# circuit_etudiant_2025.net
KiCad netlist of a schematic drawn in Altium Designer
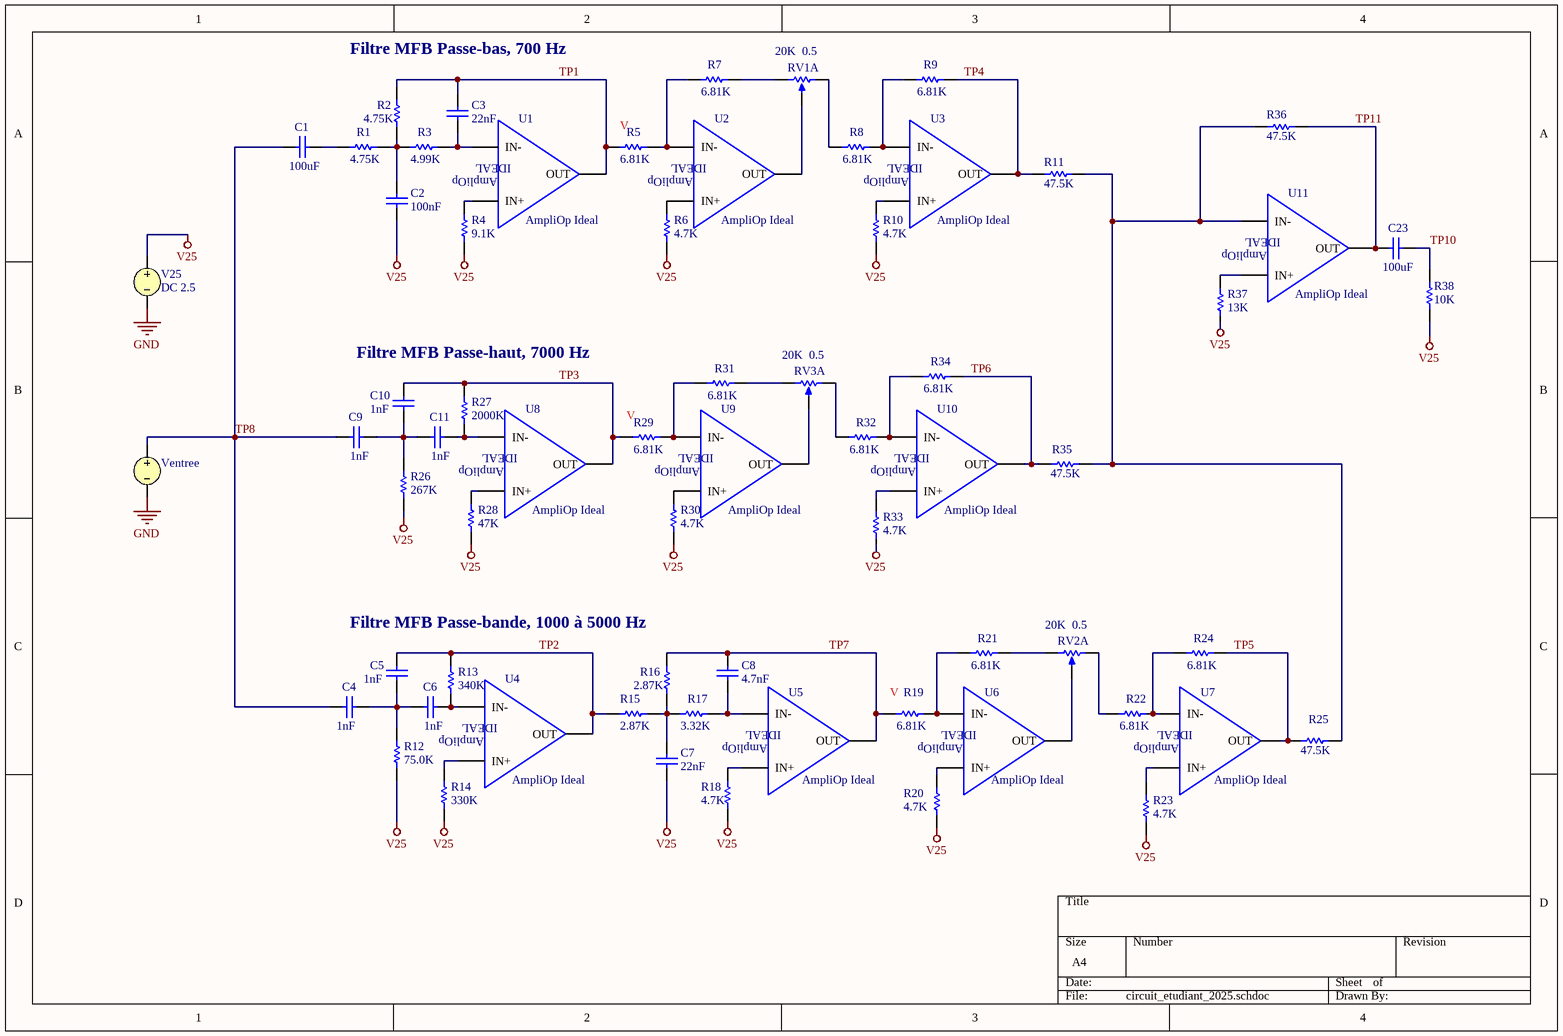
[diagram p0: circuit_etudiant_2025.schdoc]

(export (version "E")
  (design (tool "Eeschema 10.0.6"))
  (components
    (comp (ref "C1")
      (value "100uF")
      (footprint "RAD-0.3")
      (description "Capacitor")
      (fields (field (name "Comment") "Cap") (field (name "PUBLISHER") "Altium Limited"))
      (libsource (lib "Miscellaneous Devices") (part "Cap"))
    )
    (comp (ref "C2")
      (value "100nF")
      (footprint "RAD-0.3")
      (description "Capacitor")
      (fields (field (name "Comment") "Cap") (field (name "PUBLISHER") "Altium Limited"))
      (libsource (lib "Miscellaneous Devices") (part "Cap"))
    )
    (comp (ref "C3")
      (value "22nF")
      (footprint "RAD-0.3")
      (description "Capacitor")
      (fields (field (name "Comment") "Cap") (field (name "PUBLISHER") "Altium Limited"))
      (libsource (lib "Miscellaneous Devices") (part "Cap"))
    )
    (comp (ref "C4")
      (value "1nF")
      (footprint "RAD-0.3")
      (description "Capacitor")
      (fields (field (name "Comment") "Cap") (field (name "PUBLISHER") "Altium Limited"))
      (libsource (lib "Miscellaneous Devices") (part "Cap"))
    )
    (comp (ref "C5")
      (value "1nF")
      (footprint "RAD-0.3")
      (description "Capacitor")
      (fields (field (name "Comment") "Cap") (field (name "PUBLISHER") "Altium Limited"))
      (libsource (lib "Miscellaneous Devices") (part "Cap"))
    )
    (comp (ref "C6")
      (value "1nF")
      (footprint "RAD-0.3")
      (description "Capacitor")
      (fields (field (name "Comment") "Cap") (field (name "PUBLISHER") "Altium Limited"))
      (libsource (lib "Miscellaneous Devices") (part "Cap"))
    )
    (comp (ref "C7")
      (value "22nF")
      (footprint "RAD-0.3")
      (description "Capacitor")
      (fields (field (name "Comment") "Cap") (field (name "PUBLISHER") "Altium Limited"))
      (libsource (lib "Miscellaneous Devices") (part "Cap"))
    )
    (comp (ref "C8")
      (value "4.7nF")
      (footprint "RAD-0.3")
      (description "Capacitor")
      (fields (field (name "Comment") "Cap") (field (name "PUBLISHER") "Altium Limited"))
      (libsource (lib "Miscellaneous Devices") (part "Cap"))
    )
    (comp (ref "C9")
      (value "1nF")
      (footprint "RAD-0.3")
      (description "Capacitor")
      (fields (field (name "Comment") "Cap") (field (name "PUBLISHER") "Altium Limited"))
      (libsource (lib "Miscellaneous Devices") (part "Cap"))
    )
    (comp (ref "C10")
      (value "1nF")
      (footprint "RAD-0.3")
      (description "Capacitor")
      (fields (field (name "Comment") "Cap") (field (name "PUBLISHER") "Altium Limited"))
      (libsource (lib "Miscellaneous Devices") (part "Cap"))
    )
    (comp (ref "C11")
      (value "1nF")
      (footprint "RAD-0.3")
      (description "Capacitor")
      (fields (field (name "Comment") "Cap") (field (name "PUBLISHER") "Altium Limited"))
      (libsource (lib "Miscellaneous Devices") (part "Cap"))
    )
    (comp (ref "C23")
      (value "100uF")
      (footprint "RAD-0.3")
      (description "Capacitor")
      (fields (field (name "Comment") "Cap") (field (name "PUBLISHER") "Altium Limited"))
      (libsource (lib "Miscellaneous Devices") (part "Cap"))
    )
    (comp (ref "R1")
      (value "4.75K")
      (footprint "AXIAL-0.3")
      (description "Resistor")
      (fields (field (name "Comment") "Res1") (field (name "PUBLISHER") "Altium Limited"))
      (libsource (lib "Miscellaneous Devices") (part "Res1"))
    )
    (comp (ref "R2")
      (value "4.75K")
      (footprint "AXIAL-0.3")
      (description "Resistor")
      (fields (field (name "Comment") "Res1") (field (name "PUBLISHER") "Altium Limited"))
      (libsource (lib "Miscellaneous Devices") (part "Res1"))
    )
    (comp (ref "R3")
      (value "4.99K")
      (footprint "AXIAL-0.3")
      (description "Resistor")
      (fields (field (name "Comment") "Res1") (field (name "PUBLISHER") "Altium Limited"))
      (libsource (lib "Miscellaneous Devices") (part "Res1"))
    )
    (comp (ref "R4")
      (value "9.1K")
      (footprint "AXIAL-0.3")
      (description "Resistor")
      (fields (field (name "Comment") "Res1") (field (name "PUBLISHER") "Altium Limited"))
      (libsource (lib "Miscellaneous Devices") (part "Res1"))
    )
    (comp (ref "R5")
      (value "6.81K")
      (footprint "AXIAL-0.3")
      (description "Resistor")
      (fields (field (name "Comment") "Res1") (field (name "PUBLISHER") "Altium Limited"))
      (libsource (lib "Miscellaneous Devices") (part "Res1"))
    )
    (comp (ref "R6")
      (value "4.7K")
      (footprint "AXIAL-0.3")
      (description "Resistor")
      (fields (field (name "Comment") "Res1") (field (name "PUBLISHER") "Altium Limited"))
      (libsource (lib "Miscellaneous Devices") (part "Res1"))
    )
    (comp (ref "R7")
      (value "6.81K")
      (footprint "AXIAL-0.3")
      (description "Resistor")
      (fields (field (name "Comment") "Res1") (field (name "PUBLISHER") "Altium Limited"))
      (libsource (lib "Miscellaneous Devices") (part "Res1"))
    )
    (comp (ref "R8")
      (value "6.81K")
      (footprint "AXIAL-0.3")
      (description "Resistor")
      (fields (field (name "Comment") "Res1") (field (name "PUBLISHER") "Altium Limited"))
      (libsource (lib "Miscellaneous Devices") (part "Res1"))
    )
    (comp (ref "R9")
      (value "6.81K")
      (footprint "AXIAL-0.3")
      (description "Resistor")
      (fields (field (name "Comment") "Res1") (field (name "PUBLISHER") "Altium Limited"))
      (libsource (lib "Miscellaneous Devices") (part "Res1"))
    )
    (comp (ref "R10")
      (value "4.7K")
      (footprint "AXIAL-0.3")
      (description "Resistor")
      (fields (field (name "Comment") "Res1") (field (name "PUBLISHER") "Altium Limited"))
      (libsource (lib "Miscellaneous Devices") (part "Res1"))
    )
    (comp (ref "R11")
      (value "47.5K")
      (footprint "AXIAL-0.3")
      (description "Resistor")
      (fields (field (name "Comment") "Res1") (field (name "PUBLISHER") "Altium Limited"))
      (libsource (lib "Miscellaneous Devices") (part "Res1"))
    )
    (comp (ref "R12")
      (value "75.0K")
      (footprint "AXIAL-0.3")
      (description "Resistor")
      (fields (field (name "Comment") "Res1") (field (name "PUBLISHER") "Altium Limited"))
      (libsource (lib "Miscellaneous Devices") (part "Res1"))
    )
    (comp (ref "R13")
      (value "340K")
      (footprint "AXIAL-0.3")
      (description "Resistor")
      (fields (field (name "Comment") "Res1") (field (name "PUBLISHER") "Altium Limited"))
      (libsource (lib "Miscellaneous Devices") (part "Res1"))
    )
    (comp (ref "R14")
      (value "330K")
      (footprint "AXIAL-0.3")
      (description "Resistor")
      (fields (field (name "Comment") "Res1") (field (name "PUBLISHER") "Altium Limited"))
      (libsource (lib "Miscellaneous Devices") (part "Res1"))
    )
    (comp (ref "R15")
      (value "2.87K")
      (footprint "AXIAL-0.3")
      (description "Resistor")
      (fields (field (name "Comment") "Res1") (field (name "PUBLISHER") "Altium Limited"))
      (libsource (lib "Miscellaneous Devices") (part "Res1"))
    )
    (comp (ref "R16")
      (value "2.87K")
      (footprint "AXIAL-0.3")
      (description "Resistor")
      (fields (field (name "Comment") "Res1") (field (name "PUBLISHER") "Altium Limited"))
      (libsource (lib "Miscellaneous Devices") (part "Res1"))
    )
    (comp (ref "R17")
      (value "3.32K")
      (footprint "AXIAL-0.3")
      (description "Resistor")
      (fields (field (name "Comment") "Res1") (field (name "PUBLISHER") "Altium Limited"))
      (libsource (lib "Miscellaneous Devices") (part "Res1"))
    )
    (comp (ref "R18")
      (value "4.7K")
      (footprint "AXIAL-0.3")
      (description "Resistor")
      (fields (field (name "Comment") "Res1") (field (name "PUBLISHER") "Altium Limited"))
      (libsource (lib "Miscellaneous Devices") (part "Res1"))
    )
    (comp (ref "R19")
      (value "6.81K")
      (footprint "AXIAL-0.3")
      (description "Resistor")
      (fields (field (name "Comment") "Res1") (field (name "PUBLISHER") "Altium Limited"))
      (libsource (lib "Miscellaneous Devices") (part "Res1"))
    )
    (comp (ref "R20")
      (value "4.7K")
      (footprint "AXIAL-0.3")
      (description "Resistor")
      (fields (field (name "Comment") "Res1") (field (name "PUBLISHER") "Altium Limited"))
      (libsource (lib "Miscellaneous Devices") (part "Res1"))
    )
    (comp (ref "R21")
      (value "6.81K")
      (footprint "AXIAL-0.3")
      (description "Resistor")
      (fields (field (name "Comment") "Res1") (field (name "PUBLISHER") "Altium Limited"))
      (libsource (lib "Miscellaneous Devices") (part "Res1"))
    )
    (comp (ref "R22")
      (value "6.81K")
      (footprint "AXIAL-0.3")
      (description "Resistor")
      (fields (field (name "Comment") "Res1") (field (name "PUBLISHER") "Altium Limited"))
      (libsource (lib "Miscellaneous Devices") (part "Res1"))
    )
    (comp (ref "R23")
      (value "4.7K")
      (footprint "AXIAL-0.3")
      (description "Resistor")
      (fields (field (name "Comment") "Res1") (field (name "PUBLISHER") "Altium Limited"))
      (libsource (lib "Miscellaneous Devices") (part "Res1"))
    )
    (comp (ref "R24")
      (value "6.81K")
      (footprint "AXIAL-0.3")
      (description "Resistor")
      (fields (field (name "Comment") "Res1") (field (name "PUBLISHER") "Altium Limited"))
      (libsource (lib "Miscellaneous Devices") (part "Res1"))
    )
    (comp (ref "R25")
      (value "47.5K")
      (footprint "AXIAL-0.3")
      (description "Resistor")
      (fields (field (name "Comment") "Res1") (field (name "PUBLISHER") "Altium Limited"))
      (libsource (lib "Miscellaneous Devices") (part "Res1"))
    )
    (comp (ref "R26")
      (value "267K")
      (footprint "AXIAL-0.3")
      (description "Resistor")
      (fields (field (name "Comment") "Res1") (field (name "PUBLISHER") "Altium Limited"))
      (libsource (lib "Miscellaneous Devices") (part "Res1"))
    )
    (comp (ref "R27")
      (value "2000K")
      (footprint "AXIAL-0.3")
      (description "Resistor")
      (fields (field (name "Comment") "Res1") (field (name "PUBLISHER") "Altium Limited"))
      (libsource (lib "Miscellaneous Devices") (part "Res1"))
    )
    (comp (ref "R28")
      (value "47K")
      (footprint "AXIAL-0.3")
      (description "Resistor")
      (fields (field (name "Comment") "Res1") (field (name "PUBLISHER") "Altium Limited"))
      (libsource (lib "Miscellaneous Devices") (part "Res1"))
    )
    (comp (ref "R29")
      (value "6.81K")
      (footprint "AXIAL-0.3")
      (description "Resistor")
      (fields (field (name "Comment") "Res1") (field (name "PUBLISHER") "Altium Limited"))
      (libsource (lib "Miscellaneous Devices") (part "Res1"))
    )
    (comp (ref "R30")
      (value "4.7K")
      (footprint "AXIAL-0.3")
      (description "Resistor")
      (fields (field (name "Comment") "Res1") (field (name "PUBLISHER") "Altium Limited"))
      (libsource (lib "Miscellaneous Devices") (part "Res1"))
    )
    (comp (ref "R31")
      (value "6.81K")
      (footprint "AXIAL-0.3")
      (description "Resistor")
      (fields (field (name "Comment") "Res1") (field (name "PUBLISHER") "Altium Limited"))
      (libsource (lib "Miscellaneous Devices") (part "Res1"))
    )
    (comp (ref "R32")
      (value "6.81K")
      (footprint "AXIAL-0.3")
      (description "Resistor")
      (fields (field (name "Comment") "Res1") (field (name "PUBLISHER") "Altium Limited"))
      (libsource (lib "Miscellaneous Devices") (part "Res1"))
    )
    (comp (ref "R33")
      (value "4.7K")
      (footprint "AXIAL-0.3")
      (description "Resistor")
      (fields (field (name "Comment") "Res1") (field (name "PUBLISHER") "Altium Limited"))
      (libsource (lib "Miscellaneous Devices") (part "Res1"))
    )
    (comp (ref "R34")
      (value "6.81K")
      (footprint "AXIAL-0.3")
      (description "Resistor")
      (fields (field (name "Comment") "Res1") (field (name "PUBLISHER") "Altium Limited"))
      (libsource (lib "Miscellaneous Devices") (part "Res1"))
    )
    (comp (ref "R35")
      (value "47.5K")
      (footprint "AXIAL-0.3")
      (description "Resistor")
      (fields (field (name "Comment") "Res1") (field (name "PUBLISHER") "Altium Limited"))
      (libsource (lib "Miscellaneous Devices") (part "Res1"))
    )
    (comp (ref "R36")
      (value "47.5K")
      (footprint "AXIAL-0.3")
      (description "Resistor")
      (fields (field (name "Comment") "Res1") (field (name "PUBLISHER") "Altium Limited"))
      (libsource (lib "Miscellaneous Devices") (part "Res1"))
    )
    (comp (ref "R37")
      (value "13K")
      (footprint "AXIAL-0.3")
      (description "Resistor")
      (fields (field (name "Comment") "Res1") (field (name "PUBLISHER") "Altium Limited"))
      (libsource (lib "Miscellaneous Devices") (part "Res1"))
    )
    (comp (ref "R38")
      (value "10K")
      (footprint "AXIAL-0.3")
      (description "Resistor")
      (fields (field (name "Comment") "Res1") (field (name "PUBLISHER") "Altium Limited"))
      (libsource (lib "Miscellaneous Devices") (part "Res1"))
    )
    (comp (ref "RV1A")
      (value "20K")
      (footprint "VR5")
      (description "Potentiometer")
      (fields
        (field (name "SET POSITION") "0.5")
        (field (name "Comment") "RPot")
        (field (name "PUBLISHER") "Altium Limited")
      )
      (libsource (lib "Miscellaneous Devices") (part "RPot"))
    )
    (comp (ref "RV2A")
      (value "20K")
      (footprint "VR5")
      (description "Potentiometer")
      (fields
        (field (name "SET POSITION") "0.5")
        (field (name "Comment") "RPot")
        (field (name "PUBLISHER") "Altium Limited")
      )
      (libsource (lib "Miscellaneous Devices") (part "RPot"))
    )
    (comp (ref "RV3A")
      (value "20K")
      (footprint "VR5")
      (description "Potentiometer")
      (fields
        (field (name "SET POSITION") "0.5")
        (field (name "Comment") "RPot")
        (field (name "PUBLISHER") "Altium Limited")
      )
      (libsource (lib "Miscellaneous Devices") (part "RPot"))
    )
    (comp (ref "U1") (value "AmpliOp Ideal") (libsource (lib "Librarie_S2") (part "AmpliOp_ideal")))
    (comp (ref "U2") (value "AmpliOp Ideal") (libsource (lib "Librarie_S2") (part "AmpliOp_ideal")))
    (comp (ref "U3") (value "AmpliOp Ideal") (libsource (lib "Librarie_S2") (part "AmpliOp_ideal")))
    (comp (ref "U4") (value "AmpliOp Ideal") (libsource (lib "Librarie_S2") (part "AmpliOp_ideal")))
    (comp (ref "U5") (value "AmpliOp Ideal") (libsource (lib "Librarie_S2") (part "AmpliOp_ideal")))
    (comp (ref "U6") (value "AmpliOp Ideal") (libsource (lib "Librarie_S2") (part "AmpliOp_ideal")))
    (comp (ref "U7") (value "AmpliOp Ideal") (libsource (lib "Librarie_S2") (part "AmpliOp_ideal")))
    (comp (ref "U8") (value "AmpliOp Ideal") (libsource (lib "Librarie_S2") (part "AmpliOp_ideal")))
    (comp (ref "U9") (value "AmpliOp Ideal") (libsource (lib "Librarie_S2") (part "AmpliOp_ideal")))
    (comp (ref "U10") (value "AmpliOp Ideal") (libsource (lib "Librarie_S2") (part "AmpliOp_ideal")))
    (comp (ref "U11") (value "AmpliOp Ideal") (libsource (lib "Librarie_S2") (part "AmpliOp_ideal")))
    (comp (ref "V25")
      (value "DC 2.5")
      (description "Voltage Source")
      (fields (field (name "PUBLISHER") "Altium Limited"))
      (libsource (lib "Simulation Generic Components") (part "VSRC"))
    )
    (comp (ref "Ventree")
      (value "SIN(0 1 1Meg 0 0 0)")
      (description "Voltage Source")
      (fields (field (name "PUBLISHER") "Altium Limited"))
      (libsource (lib "Simulation Generic Components") (part "VSRC"))
    )
  )
  (nets
    (net (code "1") (name "/TP1") (class "Default")
      (node (ref "C3") (pin "1") (pinfunction "1_1") (pintype "passive"))
      (node (ref "R2") (pin "1") (pinfunction "1_1") (pintype "passive"))
      (node (ref "R5") (pin "1") (pinfunction "1_1") (pintype "passive"))
      (node (ref "U1") (pin "3") (pinfunction "OUT_3") (pintype "passive"))
    )
    (net (code "2") (name "/TP2") (class "Default")
      (node (ref "C5") (pin "1") (pinfunction "1_1") (pintype "passive"))
      (node (ref "R13") (pin "1") (pinfunction "1_1") (pintype "passive"))
      (node (ref "R15") (pin "1") (pinfunction "1_1") (pintype "passive"))
      (node (ref "U4") (pin "3") (pinfunction "OUT_3") (pintype "passive"))
    )
    (net (code "3") (name "/TP3") (class "Default")
      (node (ref "C10") (pin "1") (pinfunction "1_1") (pintype "passive"))
      (node (ref "R27") (pin "1") (pinfunction "1_1") (pintype "passive"))
      (node (ref "R29") (pin "1") (pinfunction "1_1") (pintype "passive"))
      (node (ref "U8") (pin "3") (pinfunction "OUT_3") (pintype "passive"))
    )
    (net (code "4") (name "/TP4") (class "Default")
      (node (ref "R11") (pin "1") (pinfunction "1_1") (pintype "passive"))
      (node (ref "R9") (pin "2") (pinfunction "2_2") (pintype "passive"))
      (node (ref "U3") (pin "3") (pinfunction "OUT_3") (pintype "passive"))
    )
    (net (code "5") (name "/TP5") (class "Default")
      (node (ref "R24") (pin "2") (pinfunction "2_2") (pintype "passive"))
      (node (ref "R25") (pin "1") (pinfunction "1_1") (pintype "passive"))
      (node (ref "U7") (pin "3") (pinfunction "OUT_3") (pintype "passive"))
    )
    (net (code "6") (name "/TP6") (class "Default")
      (node (ref "R34") (pin "2") (pinfunction "2_2") (pintype "passive"))
      (node (ref "R35") (pin "1") (pinfunction "1_1") (pintype "passive"))
      (node (ref "U10") (pin "3") (pinfunction "OUT_3") (pintype "passive"))
    )
    (net (code "7") (name "/TP7") (class "Default")
      (node (ref "C8") (pin "1") (pinfunction "1_1") (pintype "passive"))
      (node (ref "R16") (pin "1") (pinfunction "1_1") (pintype "passive"))
      (node (ref "R19") (pin "1") (pinfunction "1_1") (pintype "passive"))
      (node (ref "U5") (pin "3") (pinfunction "OUT_3") (pintype "passive"))
    )
    (net (code "8") (name "/TP8") (class "Default")
      (node (ref "C1") (pin "1") (pinfunction "1_1") (pintype "passive"))
      (node (ref "C4") (pin "1") (pinfunction "1_1") (pintype "passive"))
      (node (ref "C9") (pin "1") (pinfunction "1_1") (pintype "passive"))
      (node (ref "Ventree") (pin "1") (pinfunction "1_1") (pintype "passive"))
    )
    (net (code "9") (name "/TP10") (class "Default")
      (node (ref "C23") (pin "2") (pinfunction "2_2") (pintype "passive"))
      (node (ref "R38") (pin "2") (pinfunction "2_2") (pintype "passive"))
    )
    (net (code "10") (name "/TP11") (class "Default")
      (node (ref "C23") (pin "1") (pinfunction "1_1") (pintype "passive"))
      (node (ref "R36") (pin "2") (pinfunction "2_2") (pintype "passive"))
      (node (ref "U11") (pin "3") (pinfunction "OUT_3") (pintype "passive"))
    )
    (net (code "11") (name "GND") (class "Default")
      (node (ref "V25") (pin "2") (pinfunction "2_2") (pintype "passive"))
      (node (ref "Ventree") (pin "2") (pinfunction "2_2") (pintype "passive"))
    )
    (net (code "12") (name "Net-(C1-Pad2)") (class "Default")
      (node (ref "C1") (pin "2") (pinfunction "2_2") (pintype "passive"))
      (node (ref "R1") (pin "1") (pinfunction "1_1") (pintype "passive"))
    )
    (net (code "13") (name "Net-(C2-Pad1)") (class "Default")
      (node (ref "C2") (pin "1") (pinfunction "1_1") (pintype "passive"))
      (node (ref "R1") (pin "2") (pinfunction "2_2") (pintype "passive"))
      (node (ref "R2") (pin "2") (pinfunction "2_2") (pintype "passive"))
      (node (ref "R3") (pin "1") (pinfunction "1_1") (pintype "passive"))
    )
    (net (code "14") (name "Net-(C4-Pad2)") (class "Default")
      (node (ref "C4") (pin "2") (pinfunction "2_2") (pintype "passive"))
      (node (ref "C5") (pin "2") (pinfunction "2_2") (pintype "passive"))
      (node (ref "C6") (pin "1") (pinfunction "1_1") (pintype "passive"))
      (node (ref "R12") (pin "1") (pinfunction "1_1") (pintype "passive"))
    )
    (net (code "15") (name "Net-(C7-Pad1)") (class "Default")
      (node (ref "C7") (pin "1") (pinfunction "1_1") (pintype "passive"))
      (node (ref "R15") (pin "2") (pinfunction "2_2") (pintype "passive"))
      (node (ref "R16") (pin "2") (pinfunction "2_2") (pintype "passive"))
      (node (ref "R17") (pin "1") (pinfunction "1_1") (pintype "passive"))
    )
    (net (code "16") (name "Net-(C10-Pad2)") (class "Default")
      (node (ref "C10") (pin "2") (pinfunction "2_2") (pintype "passive"))
      (node (ref "C11") (pin "1") (pinfunction "1_1") (pintype "passive"))
      (node (ref "C9") (pin "2") (pinfunction "2_2") (pintype "passive"))
      (node (ref "R26") (pin "1") (pinfunction "1_1") (pintype "passive"))
    )
    (net (code "17") (name "Net-(RV1A-BOT)") (class "Default")
      (node (ref "R8") (pin "1") (pinfunction "1_1") (pintype "passive"))
      (node (ref "RV1A") (pin "2") (pinfunction "BOT_2") (pintype "passive"))
    )
    (net (code "18") (name "Net-(RV1A-TAP)") (class "Default")
      (node (ref "RV1A") (pin "3") (pinfunction "TAP_3") (pintype "passive"))
      (node (ref "U2") (pin "3") (pinfunction "OUT_3") (pintype "passive"))
    )
    (net (code "19") (name "Net-(RV1A-TOP)") (class "Default")
      (node (ref "R7") (pin "2") (pinfunction "2_2") (pintype "passive"))
      (node (ref "RV1A") (pin "1") (pinfunction "TOP_1") (pintype "passive"))
    )
    (net (code "20") (name "Net-(RV2A-BOT)") (class "Default")
      (node (ref "R22") (pin "1") (pinfunction "1_1") (pintype "passive"))
      (node (ref "RV2A") (pin "2") (pinfunction "BOT_2") (pintype "passive"))
    )
    (net (code "21") (name "Net-(RV2A-TAP)") (class "Default")
      (node (ref "RV2A") (pin "3") (pinfunction "TAP_3") (pintype "passive"))
      (node (ref "U6") (pin "3") (pinfunction "OUT_3") (pintype "passive"))
    )
    (net (code "22") (name "Net-(RV2A-TOP)") (class "Default")
      (node (ref "R21") (pin "2") (pinfunction "2_2") (pintype "passive"))
      (node (ref "RV2A") (pin "1") (pinfunction "TOP_1") (pintype "passive"))
    )
    (net (code "23") (name "Net-(RV3A-BOT)") (class "Default")
      (node (ref "R32") (pin "1") (pinfunction "1_1") (pintype "passive"))
      (node (ref "RV3A") (pin "2") (pinfunction "BOT_2") (pintype "passive"))
    )
    (net (code "24") (name "Net-(RV3A-TAP)") (class "Default")
      (node (ref "RV3A") (pin "3") (pinfunction "TAP_3") (pintype "passive"))
      (node (ref "U9") (pin "3") (pinfunction "OUT_3") (pintype "passive"))
    )
    (net (code "25") (name "Net-(RV3A-TOP)") (class "Default")
      (node (ref "R31") (pin "2") (pinfunction "2_2") (pintype "passive"))
      (node (ref "RV3A") (pin "1") (pinfunction "TOP_1") (pintype "passive"))
    )
    (net (code "26") (name "Net-(U1-IN+)") (class "Default")
      (node (ref "R4") (pin "1") (pinfunction "1_1") (pintype "passive"))
      (node (ref "U1") (pin "1") (pinfunction "IN+_1") (pintype "passive"))
    )
    (net (code "27") (name "Net-(U1-IN-)") (class "Default")
      (node (ref "C3") (pin "2") (pinfunction "2_2") (pintype "passive"))
      (node (ref "R3") (pin "2") (pinfunction "2_2") (pintype "passive"))
      (node (ref "U1") (pin "2") (pinfunction "IN-_2") (pintype "passive"))
    )
    (net (code "28") (name "Net-(U2-IN+)") (class "Default")
      (node (ref "R6") (pin "1") (pinfunction "1_1") (pintype "passive"))
      (node (ref "U2") (pin "1") (pinfunction "IN+_1") (pintype "passive"))
    )
    (net (code "29") (name "Net-(U2-IN-)") (class "Default")
      (node (ref "R5") (pin "2") (pinfunction "2_2") (pintype "passive"))
      (node (ref "R7") (pin "1") (pinfunction "1_1") (pintype "passive"))
      (node (ref "U2") (pin "2") (pinfunction "IN-_2") (pintype "passive"))
    )
    (net (code "30") (name "Net-(U3-IN+)") (class "Default")
      (node (ref "R10") (pin "1") (pinfunction "1_1") (pintype "passive"))
      (node (ref "U3") (pin "1") (pinfunction "IN+_1") (pintype "passive"))
    )
    (net (code "31") (name "Net-(U3-IN-)") (class "Default")
      (node (ref "R8") (pin "2") (pinfunction "2_2") (pintype "passive"))
      (node (ref "R9") (pin "1") (pinfunction "1_1") (pintype "passive"))
      (node (ref "U3") (pin "2") (pinfunction "IN-_2") (pintype "passive"))
    )
    (net (code "32") (name "Net-(U4-IN+)") (class "Default")
      (node (ref "R14") (pin "1") (pinfunction "1_1") (pintype "passive"))
      (node (ref "U4") (pin "1") (pinfunction "IN+_1") (pintype "passive"))
    )
    (net (code "33") (name "Net-(U4-IN-)") (class "Default")
      (node (ref "C6") (pin "2") (pinfunction "2_2") (pintype "passive"))
      (node (ref "R13") (pin "2") (pinfunction "2_2") (pintype "passive"))
      (node (ref "U4") (pin "2") (pinfunction "IN-_2") (pintype "passive"))
    )
    (net (code "34") (name "Net-(U5-IN+)") (class "Default")
      (node (ref "R18") (pin "1") (pinfunction "1_1") (pintype "passive"))
      (node (ref "U5") (pin "1") (pinfunction "IN+_1") (pintype "passive"))
    )
    (net (code "35") (name "Net-(U5-IN-)") (class "Default")
      (node (ref "C8") (pin "2") (pinfunction "2_2") (pintype "passive"))
      (node (ref "R17") (pin "2") (pinfunction "2_2") (pintype "passive"))
      (node (ref "U5") (pin "2") (pinfunction "IN-_2") (pintype "passive"))
    )
    (net (code "36") (name "Net-(U6-IN+)") (class "Default")
      (node (ref "R20") (pin "1") (pinfunction "1_1") (pintype "passive"))
      (node (ref "U6") (pin "1") (pinfunction "IN+_1") (pintype "passive"))
    )
    (net (code "37") (name "Net-(U6-IN-)") (class "Default")
      (node (ref "R19") (pin "2") (pinfunction "2_2") (pintype "passive"))
      (node (ref "R21") (pin "1") (pinfunction "1_1") (pintype "passive"))
      (node (ref "U6") (pin "2") (pinfunction "IN-_2") (pintype "passive"))
    )
    (net (code "38") (name "Net-(U7-IN+)") (class "Default")
      (node (ref "R23") (pin "1") (pinfunction "1_1") (pintype "passive"))
      (node (ref "U7") (pin "1") (pinfunction "IN+_1") (pintype "passive"))
    )
    (net (code "39") (name "Net-(U7-IN-)") (class "Default")
      (node (ref "R22") (pin "2") (pinfunction "2_2") (pintype "passive"))
      (node (ref "R24") (pin "1") (pinfunction "1_1") (pintype "passive"))
      (node (ref "U7") (pin "2") (pinfunction "IN-_2") (pintype "passive"))
    )
    (net (code "40") (name "Net-(U8-IN+)") (class "Default")
      (node (ref "R28") (pin "1") (pinfunction "1_1") (pintype "passive"))
      (node (ref "U8") (pin "1") (pinfunction "IN+_1") (pintype "passive"))
    )
    (net (code "41") (name "Net-(U8-IN-)") (class "Default")
      (node (ref "C11") (pin "2") (pinfunction "2_2") (pintype "passive"))
      (node (ref "R27") (pin "2") (pinfunction "2_2") (pintype "passive"))
      (node (ref "U8") (pin "2") (pinfunction "IN-_2") (pintype "passive"))
    )
    (net (code "42") (name "Net-(U9-IN+)") (class "Default")
      (node (ref "R30") (pin "1") (pinfunction "1_1") (pintype "passive"))
      (node (ref "U9") (pin "1") (pinfunction "IN+_1") (pintype "passive"))
    )
    (net (code "43") (name "Net-(U9-IN-)") (class "Default")
      (node (ref "R29") (pin "2") (pinfunction "2_2") (pintype "passive"))
      (node (ref "R31") (pin "1") (pinfunction "1_1") (pintype "passive"))
      (node (ref "U9") (pin "2") (pinfunction "IN-_2") (pintype "passive"))
    )
    (net (code "44") (name "Net-(U10-IN+)") (class "Default")
      (node (ref "R33") (pin "1") (pinfunction "1_1") (pintype "passive"))
      (node (ref "U10") (pin "1") (pinfunction "IN+_1") (pintype "passive"))
    )
    (net (code "45") (name "Net-(U10-IN-)") (class "Default")
      (node (ref "R32") (pin "2") (pinfunction "2_2") (pintype "passive"))
      (node (ref "R34") (pin "1") (pinfunction "1_1") (pintype "passive"))
      (node (ref "U10") (pin "2") (pinfunction "IN-_2") (pintype "passive"))
    )
    (net (code "46") (name "Net-(U11-IN+)") (class "Default")
      (node (ref "R37") (pin "1") (pinfunction "1_1") (pintype "passive"))
      (node (ref "U11") (pin "1") (pinfunction "IN+_1") (pintype "passive"))
    )
    (net (code "47") (name "Net-(U11-IN-)") (class "Default")
      (node (ref "R11") (pin "2") (pinfunction "2_2") (pintype "passive"))
      (node (ref "R25") (pin "2") (pinfunction "2_2") (pintype "passive"))
      (node (ref "R35") (pin "2") (pinfunction "2_2") (pintype "passive"))
      (node (ref "R36") (pin "1") (pinfunction "1_1") (pintype "passive"))
      (node (ref "U11") (pin "2") (pinfunction "IN-_2") (pintype "passive"))
    )
    (net (code "48") (name "V25") (class "Default")
      (node (ref "C2") (pin "2") (pinfunction "2_2") (pintype "passive"))
      (node (ref "C7") (pin "2") (pinfunction "2_2") (pintype "passive"))
      (node (ref "R10") (pin "2") (pinfunction "2_2") (pintype "passive"))
      (node (ref "R12") (pin "2") (pinfunction "2_2") (pintype "passive"))
      (node (ref "R14") (pin "2") (pinfunction "2_2") (pintype "passive"))
      (node (ref "R18") (pin "2") (pinfunction "2_2") (pintype "passive"))
      (node (ref "R20") (pin "2") (pinfunction "2_2") (pintype "passive"))
      (node (ref "R23") (pin "2") (pinfunction "2_2") (pintype "passive"))
      (node (ref "R26") (pin "2") (pinfunction "2_2") (pintype "passive"))
      (node (ref "R28") (pin "2") (pinfunction "2_2") (pintype "passive"))
      (node (ref "R30") (pin "2") (pinfunction "2_2") (pintype "passive"))
      (node (ref "R33") (pin "2") (pinfunction "2_2") (pintype "passive"))
      (node (ref "R37") (pin "2") (pinfunction "2_2") (pintype "passive"))
      (node (ref "R38") (pin "1") (pinfunction "1_1") (pintype "passive"))
      (node (ref "R4") (pin "2") (pinfunction "2_2") (pintype "passive"))
      (node (ref "R6") (pin "2") (pinfunction "2_2") (pintype "passive"))
      (node (ref "V25") (pin "1") (pinfunction "1_1") (pintype "passive"))
    )
  )
)
